# ESPMAX.net
KiCad netlist of a schematic drawn in EAGLE
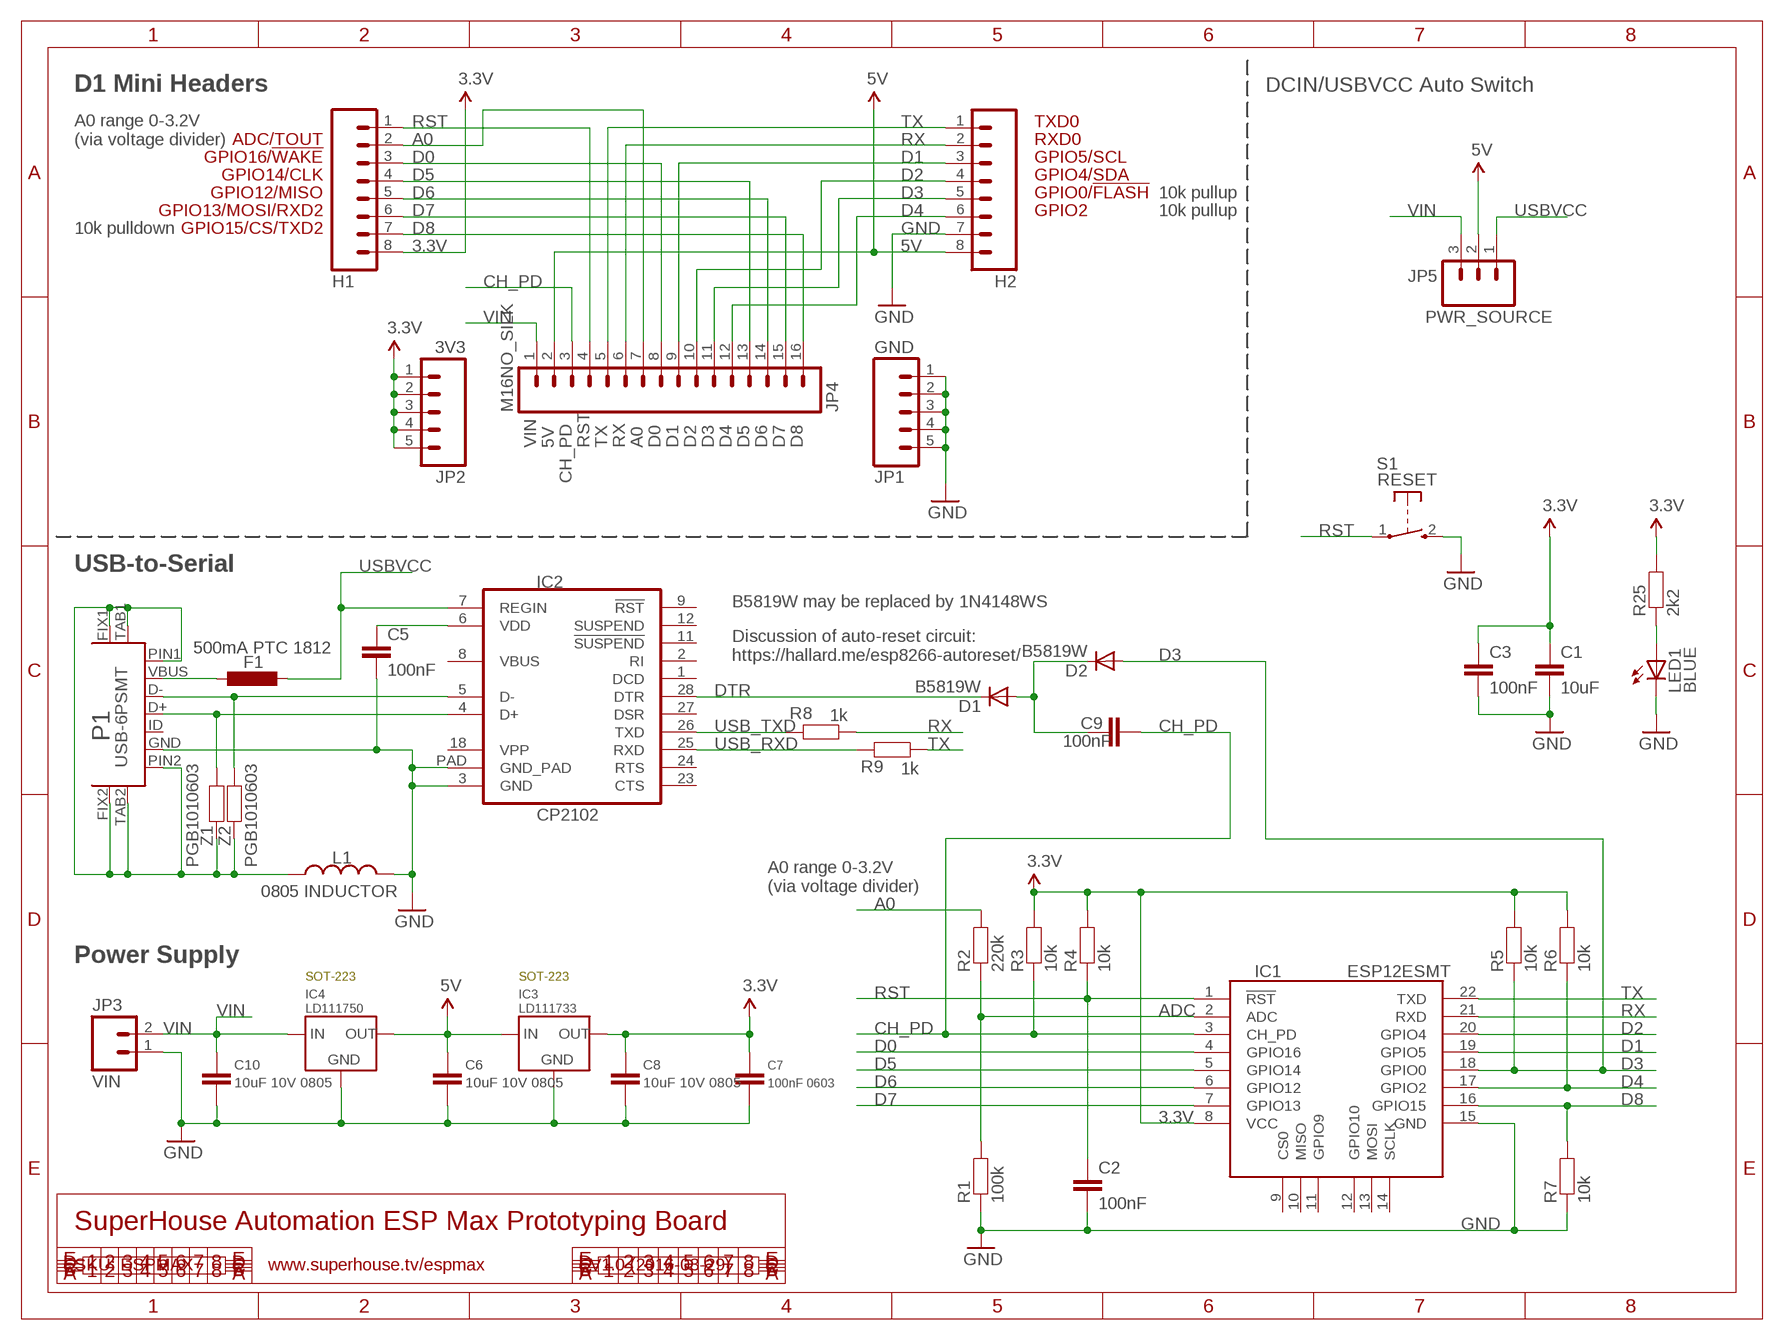
[diagram p0: schematic, sheet 1]

(export (version "E")
  (design (tool "Eeschema 10.0.6"))
  (components
    (comp (ref "C1")
      (value "10uF")
      (footprint "eagle-import:0805")
      (libsource (lib "eagle-import") (part "CAP0805"))
    )
    (comp (ref "C2")
      (value "100nF")
      (footprint "eagle-import:0603")
      (libsource (lib "eagle-import") (part "CAP0603"))
    )
    (comp (ref "C3")
      (value "100nF")
      (footprint "eagle-import:0603")
      (libsource (lib "eagle-import") (part "CAP0603"))
    )
    (comp (ref "C5")
      (value "100nF")
      (footprint "eagle-import:0603")
      (libsource (lib "eagle-import") (part "CAP0603"))
    )
    (comp (ref "C6")
      (value "10uF 10V 0805")
      (footprint "eagle-import:C0805")
      (libsource (lib "eagle-import") (part "C-EUC0805"))
    )
    (comp (ref "C7")
      (value "100nF 0603")
      (footprint "eagle-import:0603")
      (libsource (lib "eagle-import") (part "freetronics-master-v1_CAP0603"))
    )
    (comp (ref "C8")
      (value "10uF 10V 0805")
      (footprint "eagle-import:C0805")
      (libsource (lib "eagle-import") (part "C-EUC0805"))
    )
    (comp (ref "C9")
      (value "100nF")
      (footprint "eagle-import:0603")
      (libsource (lib "eagle-import") (part "CAP0603"))
    )
    (comp (ref "C10")
      (value "10uF 10V 0805")
      (footprint "eagle-import:C0805")
      (libsource (lib "eagle-import") (part "C-EUC0805"))
    )
    (comp (ref "D1")
      (value "B5819W")
      (footprint "eagle-import:SOD-323")
      (libsource (lib "eagle-import") (part "DIODESOD"))
    )
    (comp (ref "D2")
      (value "B5819W")
      (footprint "eagle-import:SOD-323")
      (libsource (lib "eagle-import") (part "DIODESOD"))
    )
    (comp (ref "F1")
      (value "500mA PTC 1812")
      (footprint "eagle-import:L1812")
      (libsource (lib "eagle-import") (part "L-EUL1812"))
    )
    (comp (ref "H1")
      (value "M08")
      (footprint "eagle-import:1X08")
      (libsource (lib "eagle-import") (part "M08"))
    )
    (comp (ref "H2")
      (value "M08")
      (footprint "eagle-import:1X08")
      (libsource (lib "eagle-import") (part "M08"))
    )
    (comp (ref "IC1")
      (value "ESP12ESMT")
      (footprint "eagle-import:ESP12E")
      (libsource (lib "eagle-import") (part "ESP12ESMT"))
    )
    (comp (ref "IC2")
      (value "CP2102")
      (footprint "eagle-import:QFN-28")
      (libsource (lib "eagle-import") (part "CP2102"))
    )
    (comp (ref "IC3")
      (value "LD111733")
      (footprint "eagle-import:SOT-223")
      (libsource (lib "eagle-import") (part "LD1117-FIXED"))
    )
    (comp (ref "IC4")
      (value "LD111750")
      (footprint "eagle-import:SOT-223")
      (libsource (lib "eagle-import") (part "LD1117-FIXED"))
    )
    (comp (ref "JP1")
      (value "GND")
      (footprint "eagle-import:1X05_NO_SILK")
      (libsource (lib "eagle-import") (part "M05NO_SILK"))
    )
    (comp (ref "JP2")
      (value "3V3")
      (footprint "eagle-import:1X05_NO_SILK")
      (libsource (lib "eagle-import") (part "M05NO_SILK"))
    )
    (comp (ref "JP3")
      (value "VIN")
      (footprint "eagle-import:SCREWTERMINAL-3.5MM-2")
      (libsource (lib "eagle-import") (part "M023.5MM"))
    )
    (comp (ref "JP4")
      (value "M16NO_SILK")
      (footprint "eagle-import:1X16_NO_SILK")
      (libsource (lib "eagle-import") (part "M16NO_SILK"))
    )
    (comp (ref "JP5")
      (value "PWR_SOURCE")
      (footprint "eagle-import:1X03")
      (libsource (lib "eagle-import") (part "M03PTH"))
    )
    (comp (ref "L1")
      (value "0805 INDUCTOR")
      (footprint "eagle-import:0805-LARGE")
      (libsource (lib "eagle-import") (part "INDUCTOR0805-LARGE"))
    )
    (comp (ref "LED1")
      (value "BLUE")
      (footprint "eagle-import:LED-0603")
      (libsource (lib "eagle-import") (part "LED0603"))
    )
    (comp (ref "P1")
      (value "USB-6PSMT")
      (footprint "eagle-import:USB-MICROB-MB05PMXX")
      (libsource (lib "eagle-import") (part "USB-6PSMT"))
    )
    (comp (ref "R1")
      (value "100k")
      (footprint "eagle-import:0603")
      (libsource (lib "eagle-import") (part "freetronics-jon_RESISTOR0603"))
    )
    (comp (ref "R2")
      (value "220k")
      (footprint "eagle-import:0603")
      (libsource (lib "eagle-import") (part "freetronics-jon_RESISTOR0603"))
    )
    (comp (ref "R3")
      (value "10k")
      (footprint "eagle-import:0603")
      (libsource (lib "eagle-import") (part "freetronics-jon_RESISTOR0603"))
    )
    (comp (ref "R4")
      (value "10k")
      (footprint "eagle-import:0603")
      (libsource (lib "eagle-import") (part "freetronics-jon_RESISTOR0603"))
    )
    (comp (ref "R5")
      (value "10k")
      (footprint "eagle-import:0603")
      (libsource (lib "eagle-import") (part "freetronics-jon_RESISTOR0603"))
    )
    (comp (ref "R6")
      (value "10k")
      (footprint "eagle-import:0603")
      (libsource (lib "eagle-import") (part "freetronics-jon_RESISTOR0603"))
    )
    (comp (ref "R7")
      (value "10k")
      (footprint "eagle-import:0603")
      (libsource (lib "eagle-import") (part "freetronics-jon_RESISTOR0603"))
    )
    (comp (ref "R8")
      (value "1k")
      (footprint "eagle-import:0603")
      (libsource (lib "eagle-import") (part "freetronics-jon_RESISTOR0603"))
    )
    (comp (ref "R9")
      (value "1k")
      (footprint "eagle-import:0603")
      (libsource (lib "eagle-import") (part "freetronics-jon_RESISTOR0603"))
    )
    (comp (ref "R25")
      (value "2k2")
      (footprint "eagle-import:0603")
      (libsource (lib "eagle-import") (part "freetronics-jon_RESISTOR0603"))
    )
    (comp (ref "S1")
      (value "RESET")
      (footprint "eagle-import:TACTILE_SWITCH_SMD_2PIN_TINY")
      (libsource (lib "eagle-import") (part "TAC_SWITCH_2PINSMT"))
    )
    (comp (ref "Z1")
      (value "PGB1010603")
      (footprint "eagle-import:0603")
      (libsource (lib "eagle-import") (part "RESISTOR0603"))
    )
    (comp (ref "Z2")
      (value "PGB1010603")
      (footprint "eagle-import:0603")
      (libsource (lib "eagle-import") (part "RESISTOR0603"))
    )
  )
  (nets
    (net (code "1") (name "/A0") (class "Default")
      (node (ref "H1") (pin "2") (pinfunction "2_2") (pintype "passive"))
      (node (ref "JP4") (pin "7") (pinfunction "7_7") (pintype "passive"))
      (node (ref "R2") (pin "2") (pinfunction "2_2") (pintype "passive"))
    )
    (net (code "2") (name "/ADC") (class "Default")
      (node (ref "IC1") (pin "2") (pinfunction "ADC_2") (pintype "input"))
      (node (ref "R1") (pin "2") (pinfunction "2_2") (pintype "passive"))
      (node (ref "R2") (pin "1") (pinfunction "1_1") (pintype "passive"))
    )
    (net (code "3") (name "/CH_PD") (class "Default")
      (node (ref "C9") (pin "2") (pinfunction "2_2") (pintype "passive"))
      (node (ref "IC1") (pin "3") (pinfunction "CH_PD_3") (pintype "input"))
      (node (ref "JP4") (pin "3") (pinfunction "3_3") (pintype "passive"))
      (node (ref "R3") (pin "1") (pinfunction "1_1") (pintype "passive"))
    )
    (net (code "4") (name "/D0") (class "Default")
      (node (ref "H1") (pin "3") (pinfunction "3_3") (pintype "passive"))
      (node (ref "IC1") (pin "4") (pinfunction "GPIO16_4") (pintype "bidirectional"))
      (node (ref "JP4") (pin "8") (pinfunction "8_8") (pintype "passive"))
    )
    (net (code "5") (name "/D1") (class "Default")
      (node (ref "H2") (pin "3") (pinfunction "3_3") (pintype "passive"))
      (node (ref "IC1") (pin "19") (pinfunction "GPIO5_19") (pintype "bidirectional"))
      (node (ref "JP4") (pin "9") (pinfunction "9_9") (pintype "passive"))
    )
    (net (code "6") (name "/D2") (class "Default")
      (node (ref "H2") (pin "4") (pinfunction "4_4") (pintype "passive"))
      (node (ref "IC1") (pin "20") (pinfunction "GPIO4_20") (pintype "bidirectional"))
      (node (ref "JP4") (pin "10") (pinfunction "10_10") (pintype "passive"))
    )
    (net (code "7") (name "/D3") (class "Default")
      (node (ref "D2") (pin "2") (pinfunction "A_2") (pintype "passive"))
      (node (ref "H2") (pin "5") (pinfunction "5_5") (pintype "passive"))
      (node (ref "IC1") (pin "18") (pinfunction "GPIO0_18") (pintype "bidirectional"))
      (node (ref "JP4") (pin "11") (pinfunction "11_11") (pintype "passive"))
      (node (ref "R5") (pin "1") (pinfunction "1_1") (pintype "passive"))
    )
    (net (code "8") (name "/D4") (class "Default")
      (node (ref "H2") (pin "6") (pinfunction "6_6") (pintype "passive"))
      (node (ref "IC1") (pin "17") (pinfunction "GPIO2_17") (pintype "bidirectional"))
      (node (ref "JP4") (pin "12") (pinfunction "12_12") (pintype "passive"))
      (node (ref "R6") (pin "1") (pinfunction "1_1") (pintype "passive"))
    )
    (net (code "9") (name "/D5") (class "Default")
      (node (ref "H1") (pin "4") (pinfunction "4_4") (pintype "passive"))
      (node (ref "IC1") (pin "5") (pinfunction "GPIO14_5") (pintype "bidirectional"))
      (node (ref "JP4") (pin "13") (pinfunction "13_13") (pintype "passive"))
    )
    (net (code "10") (name "/D6") (class "Default")
      (node (ref "H1") (pin "5") (pinfunction "5_5") (pintype "passive"))
      (node (ref "IC1") (pin "6") (pinfunction "GPIO12_6") (pintype "bidirectional"))
      (node (ref "JP4") (pin "14") (pinfunction "14_14") (pintype "passive"))
    )
    (net (code "11") (name "/D7") (class "Default")
      (node (ref "H1") (pin "6") (pinfunction "6_6") (pintype "passive"))
      (node (ref "IC1") (pin "7") (pinfunction "GPIO13_7") (pintype "bidirectional"))
      (node (ref "JP4") (pin "15") (pinfunction "15_15") (pintype "passive"))
    )
    (net (code "12") (name "/D8") (class "Default")
      (node (ref "H1") (pin "7") (pinfunction "7_7") (pintype "passive"))
      (node (ref "IC1") (pin "16") (pinfunction "GPIO15_16") (pintype "bidirectional"))
      (node (ref "JP4") (pin "16") (pinfunction "16_16") (pintype "passive"))
      (node (ref "R7") (pin "2") (pinfunction "2_2") (pintype "passive"))
    )
    (net (code "13") (name "/DTR") (class "Default")
      (node (ref "D1") (pin "1") (pinfunction "C_1") (pintype "passive"))
      (node (ref "IC2") (pin "28") (pinfunction "DTR_28") (pintype "output"))
    )
    (net (code "14") (name "/RST") (class "Default")
      (node (ref "C2") (pin "1") (pinfunction "1_1") (pintype "passive"))
      (node (ref "H1") (pin "1") (pinfunction "1_1") (pintype "passive"))
      (node (ref "IC1") (pin "1") (pinfunction "~{RST}_1") (pintype "bidirectional"))
      (node (ref "JP4") (pin "4") (pinfunction "4_4") (pintype "passive"))
      (node (ref "R4") (pin "1") (pinfunction "1_1") (pintype "passive"))
      (node (ref "S1") (pin "1") (pinfunction "P_1") (pintype "passive"))
    )
    (net (code "15") (name "/RX") (class "Default")
      (node (ref "H2") (pin "2") (pinfunction "2_2") (pintype "passive"))
      (node (ref "IC1") (pin "21") (pinfunction "RXD_21") (pintype "input"))
      (node (ref "JP4") (pin "6") (pinfunction "6_6") (pintype "passive"))
      (node (ref "R8") (pin "1") (pinfunction "1_1") (pintype "passive"))
    )
    (net (code "16") (name "/TX") (class "Default")
      (node (ref "H2") (pin "1") (pinfunction "1_1") (pintype "passive"))
      (node (ref "IC1") (pin "22") (pinfunction "TXD_22") (pintype "output"))
      (node (ref "JP4") (pin "5") (pinfunction "5_5") (pintype "passive"))
      (node (ref "R9") (pin "1") (pinfunction "1_1") (pintype "passive"))
    )
    (net (code "17") (name "/USBVCC") (class "Default")
      (node (ref "F1") (pin "2") (pinfunction "2_2") (pintype "passive"))
      (node (ref "IC2") (pin "7") (pinfunction "REGIN_7") (pintype "power_in"))
      (node (ref "JP5") (pin "1") (pinfunction "1_1") (pintype "passive"))
    )
    (net (code "18") (name "/USB_RXD") (class "Default")
      (node (ref "IC2") (pin "25") (pinfunction "RXD_25") (pintype "input"))
      (node (ref "R9") (pin "2") (pinfunction "2_2") (pintype "passive"))
    )
    (net (code "19") (name "/USB_TXD") (class "Default")
      (node (ref "IC2") (pin "26") (pinfunction "TXD_26") (pintype "output"))
      (node (ref "R8") (pin "2") (pinfunction "2_2") (pintype "passive"))
    )
    (net (code "20") (name "/VIN") (class "Default")
      (node (ref "C10") (pin "1") (pinfunction "1_1") (pintype "passive"))
      (node (ref "IC4") (pin "3") (pinfunction "IN_3") (pintype "input"))
      (node (ref "JP3") (pin "2") (pinfunction "2_2") (pintype "passive"))
      (node (ref "JP4") (pin "1") (pinfunction "1_1") (pintype "passive"))
      (node (ref "JP5") (pin "3") (pinfunction "3_3") (pintype "passive"))
    )
    (net (code "21") (name "3.3V") (class "Default")
      (node (ref "C1") (pin "1") (pinfunction "1_1") (pintype "passive"))
      (node (ref "C3") (pin "1") (pinfunction "1_1") (pintype "passive"))
      (node (ref "C7") (pin "1") (pinfunction "1_1") (pintype "passive"))
      (node (ref "C8") (pin "1") (pinfunction "1_1") (pintype "passive"))
      (node (ref "H1") (pin "8") (pinfunction "8_8") (pintype "passive"))
      (node (ref "IC1") (pin "8") (pinfunction "VCC_8") (pintype "power_in"))
      (node (ref "IC3") (pin "2") (pinfunction "OUT_2") (pintype "power_in"))
      (node (ref "IC3") (pin "4") (pinfunction "OUT_4") (pintype "power_in"))
      (node (ref "JP2") (pin "1") (pinfunction "1_1") (pintype "passive"))
      (node (ref "JP2") (pin "2") (pinfunction "2_2") (pintype "passive"))
      (node (ref "JP2") (pin "3") (pinfunction "3_3") (pintype "passive"))
      (node (ref "JP2") (pin "4") (pinfunction "4_4") (pintype "passive"))
      (node (ref "JP2") (pin "5") (pinfunction "5_5") (pintype "passive"))
      (node (ref "R25") (pin "2") (pinfunction "2_2") (pintype "passive"))
      (node (ref "R3") (pin "2") (pinfunction "2_2") (pintype "passive"))
      (node (ref "R4") (pin "2") (pinfunction "2_2") (pintype "passive"))
      (node (ref "R5") (pin "2") (pinfunction "2_2") (pintype "passive"))
      (node (ref "R6") (pin "2") (pinfunction "2_2") (pintype "passive"))
    )
    (net (code "22") (name "5V") (class "Default")
      (node (ref "C6") (pin "1") (pinfunction "1_1") (pintype "passive"))
      (node (ref "H2") (pin "8") (pinfunction "8_8") (pintype "passive"))
      (node (ref "IC3") (pin "3") (pinfunction "IN_3") (pintype "input"))
      (node (ref "IC4") (pin "2") (pinfunction "OUT_2") (pintype "power_in"))
      (node (ref "IC4") (pin "4") (pinfunction "OUT_4") (pintype "power_in"))
      (node (ref "JP4") (pin "2") (pinfunction "2_2") (pintype "passive"))
      (node (ref "JP5") (pin "2") (pinfunction "2_2") (pintype "passive"))
    )
    (net (code "23") (name "GND") (class "Default")
      (node (ref "C1") (pin "2") (pinfunction "2_2") (pintype "passive"))
      (node (ref "C10") (pin "2") (pinfunction "2_2") (pintype "passive"))
      (node (ref "C2") (pin "2") (pinfunction "2_2") (pintype "passive"))
      (node (ref "C3") (pin "2") (pinfunction "2_2") (pintype "passive"))
      (node (ref "C5") (pin "2") (pinfunction "2_2") (pintype "passive"))
      (node (ref "C6") (pin "2") (pinfunction "2_2") (pintype "passive"))
      (node (ref "C7") (pin "2") (pinfunction "2_2") (pintype "passive"))
      (node (ref "C8") (pin "2") (pinfunction "2_2") (pintype "passive"))
      (node (ref "H2") (pin "7") (pinfunction "7_7") (pintype "passive"))
      (node (ref "IC1") (pin "15") (pinfunction "GND_15") (pintype "power_in"))
      (node (ref "IC2") (pin "3") (pinfunction "GND_3") (pintype "power_in"))
      (node (ref "IC2") (pin "PAD") (pinfunction "GND_PAD_PAD") (pintype "power_in"))
      (node (ref "IC3") (pin "1") (pinfunction "GND_1") (pintype "input"))
      (node (ref "IC4") (pin "1") (pinfunction "GND_1") (pintype "input"))
      (node (ref "JP1") (pin "1") (pinfunction "1_1") (pintype "passive"))
      (node (ref "JP1") (pin "2") (pinfunction "2_2") (pintype "passive"))
      (node (ref "JP1") (pin "3") (pinfunction "3_3") (pintype "passive"))
      (node (ref "JP1") (pin "4") (pinfunction "4_4") (pintype "passive"))
      (node (ref "JP1") (pin "5") (pinfunction "5_5") (pintype "passive"))
      (node (ref "JP3") (pin "1") (pinfunction "1_1") (pintype "passive"))
      (node (ref "L1") (pin "2") (pinfunction "2_2") (pintype "passive"))
      (node (ref "LED1") (pin "C") (pinfunction "C_C") (pintype "passive"))
      (node (ref "P1") (pin "GND") (pinfunction "GND_GND") (pintype "bidirectional"))
      (node (ref "R1") (pin "1") (pinfunction "1_1") (pintype "passive"))
      (node (ref "R7") (pin "1") (pinfunction "1_1") (pintype "passive"))
      (node (ref "S1") (pin "2") (pinfunction "S_2") (pintype "passive"))
    )
    (net (code "24") (name "Net-(D1-A)") (class "Default")
      (node (ref "C9") (pin "1") (pinfunction "1_1") (pintype "passive"))
      (node (ref "D1") (pin "2") (pinfunction "A_2") (pintype "passive"))
      (node (ref "D2") (pin "1") (pinfunction "C_1") (pintype "passive"))
    )
    (net (code "25") (name "Net-(F1-Pad1)") (class "Default")
      (node (ref "F1") (pin "1") (pinfunction "1_1") (pintype "passive"))
      (node (ref "P1") (pin "VBUS") (pinfunction "VBUS_VBUS") (pintype "bidirectional"))
    )
    (net (code "26") (name "Net-(IC2-D+)") (class "Default")
      (node (ref "IC2") (pin "4") (pinfunction "D+_4") (pintype "bidirectional"))
      (node (ref "P1") (pin "D+") (pinfunction "D+_D+") (pintype "bidirectional"))
      (node (ref "Z1") (pin "1") (pinfunction "1_1") (pintype "passive"))
    )
    (net (code "27") (name "Net-(IC2-D-)") (class "Default")
      (node (ref "IC2") (pin "5") (pinfunction "D-_5") (pintype "bidirectional"))
      (node (ref "P1") (pin "D-") (pinfunction "D-_D-") (pintype "bidirectional"))
      (node (ref "Z2") (pin "1") (pinfunction "1_1") (pintype "passive"))
    )
    (net (code "28") (name "Net-(IC2-VDD)") (class "Default")
      (node (ref "C5") (pin "1") (pinfunction "1_1") (pintype "passive"))
      (node (ref "IC2") (pin "6") (pinfunction "VDD_6") (pintype "power_in"))
    )
    (net (code "29") (name "Net-(L1-Pad1)") (class "Default")
      (node (ref "L1") (pin "1") (pinfunction "1_1") (pintype "passive"))
      (node (ref "P1") (pin "FIX1") (pinfunction "FIX1_FIX1") (pintype "bidirectional"))
      (node (ref "P1") (pin "FIX2") (pinfunction "FIX2_FIX2") (pintype "bidirectional"))
      (node (ref "P1") (pin "PIN1") (pinfunction "PIN1_PIN1") (pintype "bidirectional"))
      (node (ref "P1") (pin "PIN2") (pinfunction "PIN2_PIN2") (pintype "bidirectional"))
      (node (ref "P1") (pin "TAB1") (pinfunction "TAB1_TAB1") (pintype "bidirectional"))
      (node (ref "P1") (pin "TAB2") (pinfunction "TAB2_TAB2") (pintype "bidirectional"))
      (node (ref "Z1") (pin "2") (pinfunction "2_2") (pintype "passive"))
      (node (ref "Z2") (pin "2") (pinfunction "2_2") (pintype "passive"))
    )
    (net (code "30") (name "Net-(LED1-PadA)") (class "Default")
      (node (ref "LED1") (pin "A") (pinfunction "A_A") (pintype "passive"))
      (node (ref "R25") (pin "1") (pinfunction "1_1") (pintype "passive"))
    )
    (net (code "31") (name "unconnected-(IC1-CS0-Pad9)") (class "Default")
      (node (ref "IC1") (pin "9") (pinfunction "CS0_9") (pintype "bidirectional"))
    )
    (net (code "32") (name "unconnected-(IC1-GPIO9-Pad11)") (class "Default")
      (node (ref "IC1") (pin "11") (pinfunction "GPIO9_11") (pintype "bidirectional"))
    )
    (net (code "33") (name "unconnected-(IC1-GPIO10-Pad12)") (class "Default")
      (node (ref "IC1") (pin "12") (pinfunction "GPIO10_12") (pintype "bidirectional"))
    )
    (net (code "34") (name "unconnected-(IC1-MISO-Pad10)") (class "Default")
      (node (ref "IC1") (pin "10") (pinfunction "MISO_10") (pintype "bidirectional"))
    )
    (net (code "35") (name "unconnected-(IC1-MOSI-Pad13)") (class "Default")
      (node (ref "IC1") (pin "13") (pinfunction "MOSI_13") (pintype "bidirectional"))
    )
    (net (code "36") (name "unconnected-(IC1-SCLK-Pad14)") (class "Default")
      (node (ref "IC1") (pin "14") (pinfunction "SCLK_14") (pintype "bidirectional"))
    )
    (net (code "37") (name "unconnected-(IC2-CTS-Pad23)") (class "Default")
      (node (ref "IC2") (pin "23") (pinfunction "CTS_23") (pintype "input"))
    )
    (net (code "38") (name "unconnected-(IC2-DCD-Pad1)") (class "Default")
      (node (ref "IC2") (pin "1") (pinfunction "DCD_1") (pintype "input"))
    )
    (net (code "39") (name "unconnected-(IC2-DSR-Pad27)") (class "Default")
      (node (ref "IC2") (pin "27") (pinfunction "DSR_27") (pintype "input"))
    )
    (net (code "40") (name "unconnected-(IC2-RI-Pad2)") (class "Default")
      (node (ref "IC2") (pin "2") (pinfunction "RI_2") (pintype "input"))
    )
    (net (code "41") (name "unconnected-(IC2-RTS-Pad24)") (class "Default")
      (node (ref "IC2") (pin "24") (pinfunction "RTS_24") (pintype "output"))
    )
    (net (code "42") (name "unconnected-(IC2-SUSPEND-Pad12)") (class "Default")
      (node (ref "IC2") (pin "12") (pinfunction "SUSPEND_12") (pintype "output"))
    )
    (net (code "43") (name "unconnected-(IC2-VBUS-Pad8)") (class "Default")
      (node (ref "IC2") (pin "8") (pinfunction "VBUS_8") (pintype "bidirectional"))
    )
    (net (code "44") (name "unconnected-(IC2-VPP-Pad18)") (class "Default")
      (node (ref "IC2") (pin "18") (pinfunction "VPP_18") (pintype "bidirectional"))
    )
    (net (code "45") (name "unconnected-(IC2-~{RST}-Pad9)") (class "Default")
      (node (ref "IC2") (pin "9") (pinfunction "~{RST}_9") (pintype "bidirectional"))
    )
    (net (code "46") (name "unconnected-(IC2-~{SUSPEND}-Pad11)") (class "Default")
      (node (ref "IC2") (pin "11") (pinfunction "~{SUSPEND}_11") (pintype "output"))
    )
    (net (code "47") (name "unconnected-(P1-PadID)") (class "Default")
      (node (ref "P1") (pin "ID") (pinfunction "ID_ID") (pintype "bidirectional"))
    )
  )
)
